# Control.net
KiCad netlist of a schematic drawn in Altium Designer
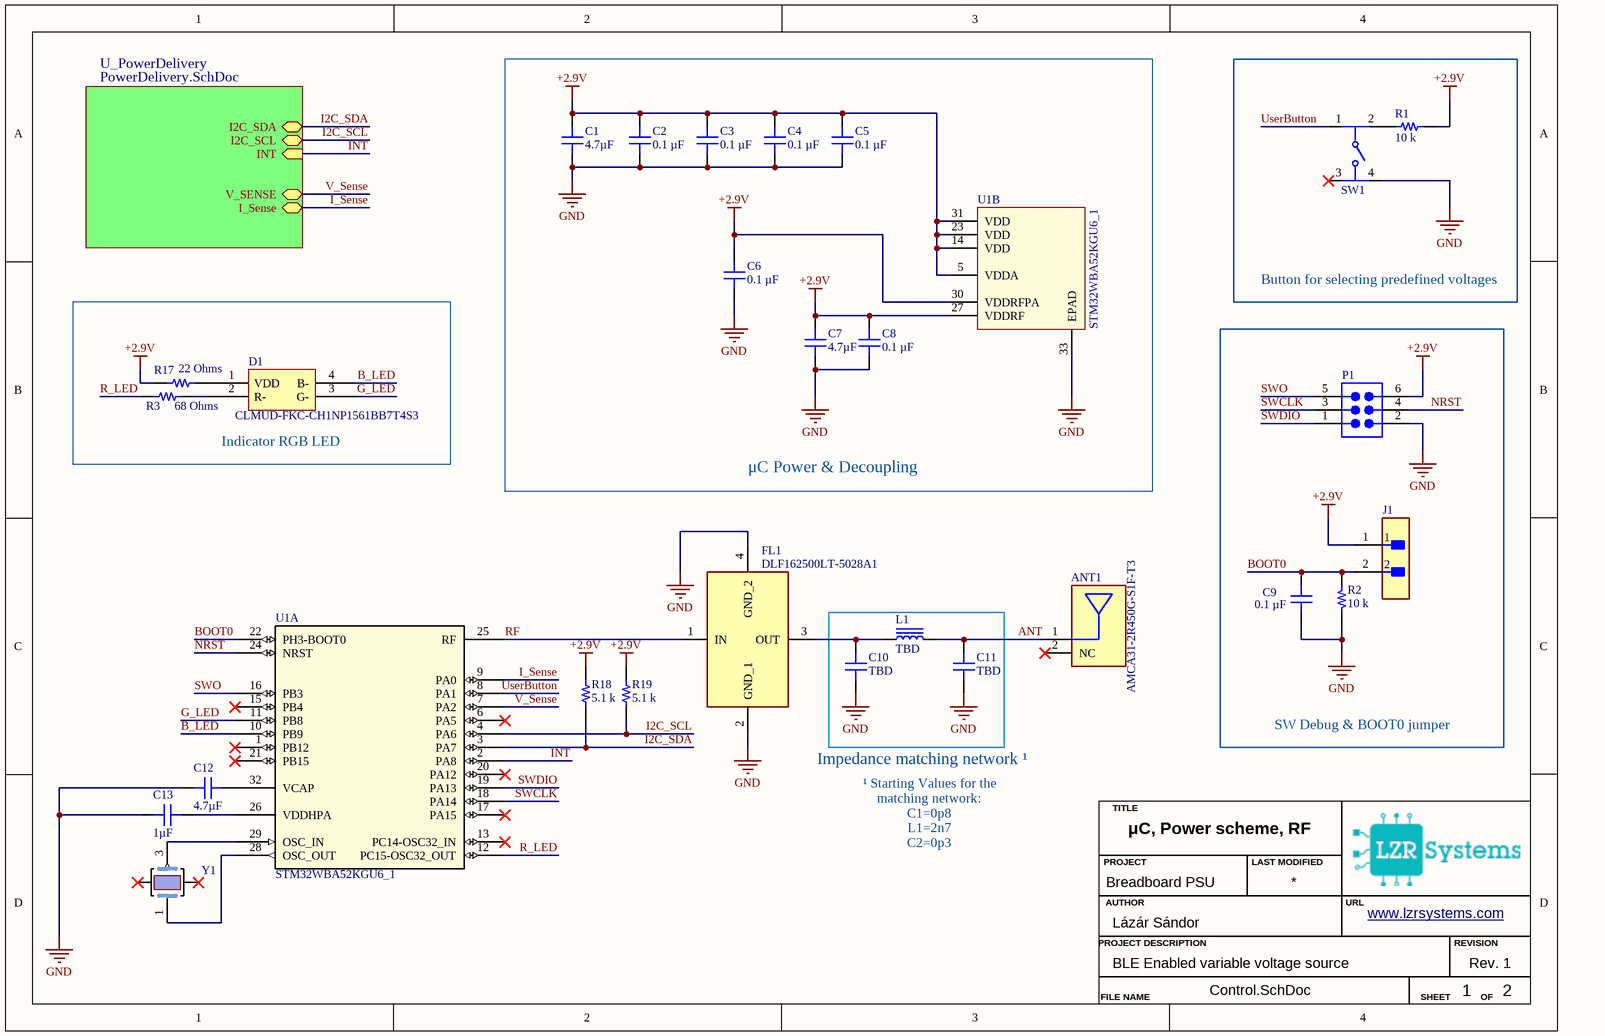
[diagram p0: Control.SchDoc]

(export (version "E")
  (design (tool "Eeschema 10.0.6"))
  (components
    (comp (ref "ANT1")
      (value "AMCA31-2R450G-S1F-T3")
      (footprint "FP-AMCA31-MFG")
      (description "Chip Dielectric Antenna; 1dBi; 2450MHz; T/R")
      (libsource (lib "Sandor Lazar") (part "feefd54aed95757a858c12fc87bd8d5"))
    )
    (comp (ref "C1")
      (value "4.7µF")
      (footprint "CAP 0805_2012")
      (description "CAP CER 4.7UF 10V X5R 0805")
      (fields
        (field (name "PART NUMBER") "0805ZD475KAT2A")
        (field (name "CAPACITANCE") "4.7µF")
        (field (name "MANUFACTURER") "AVX Corporation")
      )
      (libsource (lib "Celestial Altium Library - altium_library") (part "Capacitor"))
    )
    (comp (ref "C2")
      (value "0.1 µF")
      (footprint "CAP 0805_2012")
      (description "CAP CER 0.1UF 50V X7R 0805")
      (fields
        (field (name "PART NUMBER") "KGM21NR71H104MT")
        (field (name "CAPACITANCE") "0.1 µF")
        (field (name "MANUFACTURER") "KYOCERA AVX")
      )
      (libsource (lib "Celestial Altium Library - altium_library") (part "Capacitor"))
    )
    (comp (ref "C3")
      (value "0.1 µF")
      (footprint "CAP 0805_2012")
      (description "CAP CER 0.1UF 50V X7R 0805")
      (fields
        (field (name "PART NUMBER") "KGM21NR71H104MT")
        (field (name "CAPACITANCE") "0.1 µF")
        (field (name "MANUFACTURER") "KYOCERA AVX")
      )
      (libsource (lib "Celestial Altium Library - altium_library") (part "Capacitor"))
    )
    (comp (ref "C4")
      (value "0.1 µF")
      (footprint "CAP 0805_2012")
      (description "CAP CER 0.1UF 50V X7R 0805")
      (fields
        (field (name "PART NUMBER") "KGM21NR71H104MT")
        (field (name "CAPACITANCE") "0.1 µF")
        (field (name "MANUFACTURER") "KYOCERA AVX")
      )
      (libsource (lib "Celestial Altium Library - altium_library") (part "Capacitor"))
    )
    (comp (ref "C5")
      (value "0.1 µF")
      (footprint "CAP 0805_2012")
      (description "CAP CER 0.1UF 50V X7R 0805")
      (fields
        (field (name "PART NUMBER") "KGM21NR71H104MT")
        (field (name "CAPACITANCE") "0.1 µF")
        (field (name "MANUFACTURER") "KYOCERA AVX")
      )
      (libsource (lib "Celestial Altium Library - altium_library") (part "Capacitor"))
    )
    (comp (ref "C6")
      (value "0.1 µF")
      (footprint "CAP 0805_2012")
      (description "CAP CER 0.1UF 50V X7R 0805")
      (fields
        (field (name "PART NUMBER") "KGM21NR71H104MT")
        (field (name "CAPACITANCE") "0.1 µF")
        (field (name "MANUFACTURER") "KYOCERA AVX")
      )
      (libsource (lib "Celestial Altium Library - altium_library") (part "Capacitor"))
    )
    (comp (ref "C7")
      (value "4.7µF")
      (footprint "CAP 0805_2012")
      (description "CAP CER 4.7UF 10V X5R 0805")
      (fields
        (field (name "PART NUMBER") "0805ZD475KAT2A")
        (field (name "CAPACITANCE") "4.7µF")
        (field (name "MANUFACTURER") "AVX Corporation")
      )
      (libsource (lib "Celestial Altium Library - altium_library") (part "Capacitor"))
    )
    (comp (ref "C8")
      (value "0.1 µF")
      (footprint "CAP 0805_2012")
      (description "CAP CER 0.1UF 50V X7R 0805")
      (fields
        (field (name "PART NUMBER") "KGM21NR71H104MT")
        (field (name "CAPACITANCE") "0.1 µF")
        (field (name "MANUFACTURER") "KYOCERA AVX")
      )
      (libsource (lib "Celestial Altium Library - altium_library") (part "Capacitor"))
    )
    (comp (ref "C9")
      (value "0.1 µF")
      (footprint "CAP 0805_2012")
      (description "CAP CER 0.1UF 50V X7R 0805")
      (fields
        (field (name "PART NUMBER") "KGM21NR71H104MT")
        (field (name "CAPACITANCE") "0.1 µF")
        (field (name "MANUFACTURER") "KYOCERA AVX")
      )
      (libsource (lib "Celestial Altium Library - altium_library") (part "Capacitor"))
    )
    (comp (ref "C10")
      (value "3.6 pF")
      (footprint "CAP 0402_1005")
      (description "CAP CER 3.6PF 200V C0G/NP0 0402")
      (fields
        (field (name "PART NUMBER") "600L3R6AT200T")
        (field (name "CAPACITANCE") "TBD")
        (field (name "MANUFACTURER") "American Technical Ceramics")
      )
      (libsource (lib "Celestial Altium Library - altium_library") (part "Capacitor"))
    )
    (comp (ref "C11")
      (value "3.6 pF")
      (footprint "CAP 0402_1005")
      (description "CAP CER 3.6PF 200V C0G/NP0 0402")
      (fields
        (field (name "PART NUMBER") "600L3R6AT200T")
        (field (name "CAPACITANCE") "TBD")
        (field (name "MANUFACTURER") "American Technical Ceramics")
      )
      (libsource (lib "Celestial Altium Library - altium_library") (part "Capacitor"))
    )
    (comp (ref "C12")
      (value "4.7µF")
      (footprint "CAP 0805_2012")
      (description "CAP CER 4.7UF 10V X5R 0805")
      (fields
        (field (name "PART NUMBER") "0805ZD475KAT2A")
        (field (name "CAPACITANCE") "4.7µF")
        (field (name "MANUFACTURER") "AVX Corporation")
      )
      (libsource (lib "Celestial Altium Library - altium_library") (part "Capacitor"))
    )
    (comp (ref "C13")
      (value "1µF")
      (footprint "CAP 0805_2012")
      (description "CAP CER 1UF 25V X7R 0805")
      (fields
        (field (name "PART NUMBER") "08053C105KAT2A")
        (field (name "CAPACITANCE") "1µF")
        (field (name "MANUFACTURER") "AVX Corporation")
      )
      (libsource (lib "Celestial Altium Library - altium_library") (part "Capacitor"))
    )
    (comp (ref "D1")
      (value "CLMUD-FKC-CH1NP1561BB7T4S3")
      (footprint "SON70P150X100-4N")
      (description "Cree LED RGB LED Common Annode If=10mA Vf = 1.9/2.6/2.7")
      (libsource (lib "Sandor Lazar") (part "CLMUD-FKC-CH1NP1561BB7T4S3-Symbol-1"))
    )
    (comp (ref "FL1")
      (value "DLF162500LT-5028A1")
      (footprint "SamacSys:DLF162500LT5028A1")
      (description "Filter")
      (fields (field (name "MOUSER PART NUMBER") "810-DLF16250LT5028A1"))
      (libsource (lib "*") (part "DLF162500LT-5028A1"))
    )
    (comp (ref "J1")
      (value "TSW-102-12-T-S")
      (footprint "FP-TSW-102-12-T-S-MFG")
      (description "Pin Header, Board-to-Board, 2.54 mm, 1 Rows, 2 Contacts, Through Hole, TSW Series")
      (libsource (lib "Sandor Lazar") (part "3bc925449376181038e59eaffc5286c"))
    )
    (comp (ref "L1")
      (value "TBD")
      (footprint "IND 0402_1005")
      (description "FIXED IND 3.9NH 750MA 140MOHM SM")
      (fields
        (field (name "PART NUMBER") "LQG15HS3N9C02D")
        (field (name "MANUFACTURER") "Murata Electronics")
      )
      (libsource (lib "Celestial Altium Library - altium_library") (part "Inductor"))
    )
    (comp (ref "P1")
      (value "MTLW-103-06-G-D-180")
      (footprint "SMTC-MTLW-103-06-X-D-180")
      (description "Pin Header, Board-to-Board, 2.54 mm, 2 Rows, 6 Contacts, Through Hole, MTLW Series")
      (libsource (lib "Sandor Lazar") (part "SMTC-MTLW-103-06-X-D-180"))
    )
    (comp (ref "R1")
      (value "10 k")
      (footprint "RES 0805_2012")
      (description "RES 10K OHM 0.1% 1/10W 0805")
      (fields
        (field (name "PART NUMBER") "RNCS0805BKE10K0")
        (field (name "MANUFACTURER") "Stackpole Electronics Inc")
      )
      (libsource (lib "Celestial Altium Library - altium_library") (part "Resistor"))
    )
    (comp (ref "R2")
      (value "10 k")
      (footprint "RES 0805_2012")
      (description "RES 10K OHM 0.1% 1/10W 0805")
      (fields
        (field (name "PART NUMBER") "RNCS0805BKE10K0")
        (field (name "MANUFACTURER") "Stackpole Electronics Inc")
      )
      (libsource (lib "Celestial Altium Library - altium_library") (part "Resistor"))
    )
    (comp (ref "R3")
      (value "68 Ohms")
      (footprint "YAGEO RES 0805_2012")
      (description "RES 68.1 OHM 1% 1/8W 0805")
      (fields (field (name "PART NUMBER") "RC0805FR-0768R1L") (field (name "MANUFACTURER") "Yageo"))
      (libsource (lib "Celestial Altium Library - altium_library") (part "Resistor"))
    )
    (comp (ref "R17")
      (value "22 Ohms")
      (footprint "RES 0805_2012")
      (description "RES 22 OHM 5% 1/8W 0805")
      (fields (field (name "PART NUMBER") "SFR10EZPJ220") (field (name "MANUFACTURER") "Rohm Semiconductor"))
      (libsource (lib "Celestial Altium Library - altium_library") (part "Resistor"))
    )
    (comp (ref "R18")
      (value "5.1 k")
      (footprint "YAGEO RES 0805_2012")
      (description "RES SMD 5.1K OHM 0.1% 1/8W 0805")
      (fields (field (name "PART NUMBER") "RT0805BRD075K1L") (field (name "MANUFACTURER") "Yageo"))
      (libsource (lib "Celestial Altium Library - altium_library") (part "Resistor"))
    )
    (comp (ref "R19")
      (value "5.1 k")
      (footprint "YAGEO RES 0805_2012")
      (description "RES SMD 5.1K OHM 0.1% 1/8W 0805")
      (fields (field (name "PART NUMBER") "RT0805BRD075K1L") (field (name "MANUFACTURER") "Yageo"))
      (libsource (lib "Celestial Altium Library - altium_library") (part "Resistor"))
    )
    (comp (ref "SW1")
      (value "TL1105AF160Q")
      (footprint "FP-TL1105AF160Q-MFG")
      (description "Switch Tactile N.O. SPST Round Button PC Pins 0.05A 50VDC 1.57N Thru-Hole")
      (libsource (lib "Sandor Lazar") (part "82b636f13fd696edb7519609c0a8a76"))
    )
    (comp (ref "U1")
      (value "STM32WBA52KGU6_1")
      (footprint "UFQFPN-32_STM")
      (fields
        (field (name "MANUFACTURER_PART_NUMBER") "STM32WBA52KGU6")
        (field (name "COPYRIGHT") "Copyright (C) 2025 Ultra Librarian. All rights reserved.")
      )
      (libsource (lib "Sandor Lazar") (part "STM32WBA52KGU6_1"))
    )
    (comp (ref "Y1")
      (value "XRCGB32M000F2P01R0")
      (footprint "SamacSys:XRCGB")
      (description "Crystal or Oscillator")
      (fields (field (name "MOUSER PART NUMBER") "81-XRCGB32M000F2P01R"))
      (libsource (lib "SamacSys") (part "XRCGB32M000F2P01R0"))
    )
  )
  (nets
    (net (code "1") (name "+2.9V") (class "Default")
      (node (ref "C1") (pin "2") (pinfunction "2_2") (pintype "passive"))
      (node (ref "C2") (pin "2") (pinfunction "2_2") (pintype "passive"))
      (node (ref "C3") (pin "2") (pinfunction "2_2") (pintype "passive"))
      (node (ref "C4") (pin "2") (pinfunction "2_2") (pintype "passive"))
      (node (ref "C5") (pin "2") (pinfunction "2_2") (pintype "passive"))
      (node (ref "C6") (pin "2") (pinfunction "2_2") (pintype "passive"))
      (node (ref "C7") (pin "2") (pinfunction "2_2") (pintype "passive"))
      (node (ref "C8") (pin "2") (pinfunction "2_2") (pintype "passive"))
      (node (ref "J1") (pin "1") (pinfunction "1_1") (pintype "passive"))
      (node (ref "P1") (pin "6") (pinfunction "6_6") (pintype "passive"))
      (node (ref "R1") (pin "2") (pinfunction "2_2") (pintype "passive"))
      (node (ref "R17") (pin "2") (pinfunction "2_2") (pintype "passive"))
      (node (ref "R18") (pin "2") (pinfunction "2_2") (pintype "passive"))
      (node (ref "R19") (pin "2") (pinfunction "2_2") (pintype "passive"))
      (node (ref "U1") (pin "14") (pinfunction "VDD_14") (pintype "power_in"))
      (node (ref "U1") (pin "23") (pinfunction "VDD_23") (pintype "power_in"))
      (node (ref "U1") (pin "27") (pinfunction "VDDRF_27") (pintype "power_in"))
      (node (ref "U1") (pin "30") (pinfunction "VDDRFPA_30") (pintype "power_in"))
      (node (ref "U1") (pin "31") (pinfunction "VDD_31") (pintype "power_in"))
      (node (ref "U1") (pin "5") (pinfunction "VDDA_5") (pintype "power_in"))
    )
    (net (code "2") (name "/ANT") (class "Default")
      (node (ref "ANT1") (pin "1") (pinfunction "Feed_Point_1") (pintype "passive"))
      (node (ref "C11") (pin "2") (pinfunction "2_2") (pintype "passive"))
      (node (ref "L1") (pin "2") (pinfunction "2_2") (pintype "passive"))
    )
    (net (code "3") (name "/BOOT0") (class "Default")
      (node (ref "C9") (pin "2") (pinfunction "2_2") (pintype "passive"))
      (node (ref "J1") (pin "2") (pinfunction "2_2") (pintype "passive"))
      (node (ref "R2") (pin "2") (pinfunction "2_2") (pintype "passive"))
      (node (ref "U1") (pin "22") (pinfunction "PH3-BOOT0_22") (pintype "bidirectional"))
    )
    (net (code "4") (name "/B_LED") (class "Default")
      (node (ref "D1") (pin "4") (pinfunction "B-_4") (pintype "passive"))
      (node (ref "U1") (pin "10") (pinfunction "PB9_10") (pintype "bidirectional"))
    )
    (net (code "5") (name "/G_LED") (class "Default")
      (node (ref "D1") (pin "3") (pinfunction "G-_3") (pintype "passive"))
      (node (ref "U1") (pin "11") (pinfunction "PB8_11") (pintype "bidirectional"))
    )
    (net (code "6") (name "/I2C_SCL") (class "Default")
      (node (ref "R19") (pin "1") (pinfunction "1_1") (pintype "passive"))
      (node (ref "U1") (pin "4") (pinfunction "PA6_4") (pintype "bidirectional"))
    )
    (net (code "7") (name "/I2C_SDA") (class "Default")
      (node (ref "R18") (pin "1") (pinfunction "1_1") (pintype "passive"))
      (node (ref "U1") (pin "3") (pinfunction "PA7_3") (pintype "bidirectional"))
    )
    (net (code "8") (name "/INT") (class "Default")
      (node (ref "U1") (pin "2") (pinfunction "PA8_2") (pintype "bidirectional"))
    )
    (net (code "9") (name "/I_Sense") (class "Default")
      (node (ref "U1") (pin "9") (pinfunction "PA0_9") (pintype "bidirectional"))
    )
    (net (code "10") (name "/NRST") (class "Default")
      (node (ref "P1") (pin "4") (pinfunction "4_4") (pintype "passive"))
      (node (ref "U1") (pin "24") (pinfunction "NRST_24") (pintype "bidirectional"))
    )
    (net (code "11") (name "/RF") (class "Default")
      (node (ref "FL1") (pin "1") (pinfunction "IN_1") (pintype "passive"))
      (node (ref "U1") (pin "25") (pinfunction "RF_25") (pintype "passive"))
    )
    (net (code "12") (name "/R_LED") (class "Default")
      (node (ref "R3") (pin "1") (pinfunction "1_1") (pintype "passive"))
      (node (ref "U1") (pin "12") (pinfunction "PC15-OSC32_OUT_12") (pintype "bidirectional"))
    )
    (net (code "13") (name "/SWCLK") (class "Default")
      (node (ref "P1") (pin "3") (pinfunction "3_3") (pintype "passive"))
      (node (ref "U1") (pin "18") (pinfunction "PA14_18") (pintype "bidirectional"))
    )
    (net (code "14") (name "/SWDIO") (class "Default")
      (node (ref "P1") (pin "1") (pinfunction "1_1") (pintype "passive"))
      (node (ref "U1") (pin "19") (pinfunction "PA13_19") (pintype "bidirectional"))
    )
    (net (code "15") (name "/SWO") (class "Default")
      (node (ref "P1") (pin "5") (pinfunction "5_5") (pintype "passive"))
      (node (ref "U1") (pin "16") (pinfunction "PB3_16") (pintype "bidirectional"))
    )
    (net (code "16") (name "/UserButton") (class "Default")
      (node (ref "SW1") (pin "1") (pinfunction "1_1") (pintype "passive"))
      (node (ref "U1") (pin "8") (pinfunction "PA1_8") (pintype "bidirectional"))
    )
    (net (code "17") (name "/V_Sense") (class "Default")
      (node (ref "U1") (pin "7") (pinfunction "PA2_7") (pintype "bidirectional"))
    )
    (net (code "18") (name "GND") (class "Default")
      (node (ref "C1") (pin "1") (pinfunction "1_1") (pintype "passive"))
      (node (ref "C10") (pin "1") (pinfunction "1_1") (pintype "passive"))
      (node (ref "C11") (pin "1") (pinfunction "1_1") (pintype "passive"))
      (node (ref "C12") (pin "1") (pinfunction "1_1") (pintype "passive"))
      (node (ref "C13") (pin "2") (pinfunction "2_2") (pintype "passive"))
      (node (ref "C2") (pin "1") (pinfunction "1_1") (pintype "passive"))
      (node (ref "C3") (pin "1") (pinfunction "1_1") (pintype "passive"))
      (node (ref "C4") (pin "1") (pinfunction "1_1") (pintype "passive"))
      (node (ref "C5") (pin "1") (pinfunction "1_1") (pintype "passive"))
      (node (ref "C6") (pin "1") (pinfunction "1_1") (pintype "passive"))
      (node (ref "C7") (pin "1") (pinfunction "1_1") (pintype "passive"))
      (node (ref "C8") (pin "1") (pinfunction "1_1") (pintype "passive"))
      (node (ref "C9") (pin "1") (pinfunction "1_1") (pintype "passive"))
      (node (ref "FL1") (pin "2") (pinfunction "GND_1_2") (pintype "passive"))
      (node (ref "FL1") (pin "4") (pinfunction "GND_2_4") (pintype "passive"))
      (node (ref "P1") (pin "2") (pinfunction "2_2") (pintype "passive"))
      (node (ref "R2") (pin "1") (pinfunction "1_1") (pintype "passive"))
      (node (ref "SW1") (pin "4") (pinfunction "4_4") (pintype "passive"))
      (node (ref "U1") (pin "33") (pinfunction "EPAD_33") (pintype "passive"))
    )
    (net (code "19") (name "Net-(D1-R-)") (class "Default")
      (node (ref "D1") (pin "2") (pinfunction "R-_2") (pintype "passive"))
      (node (ref "R3") (pin "2") (pinfunction "2_2") (pintype "passive"))
    )
    (net (code "20") (name "Net-(D1-VDD)") (class "Default")
      (node (ref "D1") (pin "1") (pinfunction "VDD_1") (pintype "passive"))
      (node (ref "R17") (pin "1") (pinfunction "1_1") (pintype "passive"))
    )
    (net (code "21") (name "Net-(FL1-OUT)") (class "Default")
      (node (ref "C10") (pin "2") (pinfunction "2_2") (pintype "passive"))
      (node (ref "FL1") (pin "3") (pinfunction "OUT_3") (pintype "passive"))
      (node (ref "L1") (pin "1") (pinfunction "1_1") (pintype "passive"))
    )
    (net (code "22") (name "Net-(R1-Pad1)") (class "Default")
      (node (ref "R1") (pin "1") (pinfunction "1_1") (pintype "passive"))
      (node (ref "SW1") (pin "2") (pinfunction "2_2") (pintype "passive"))
    )
    (net (code "23") (name "Net-(U1A-OSC_IN)") (class "Default")
      (node (ref "U1") (pin "29") (pinfunction "OSC_IN_29") (pintype "input"))
      (node (ref "Y1") (pin "3") (pinfunction "XTAL_2_3") (pintype "output"))
    )
    (net (code "24") (name "Net-(U1A-OSC_OUT)") (class "Default")
      (node (ref "U1") (pin "28") (pinfunction "OSC_OUT_28") (pintype "output"))
      (node (ref "Y1") (pin "1") (pinfunction "XTAL_1_1") (pintype "passive"))
    )
    (net (code "25") (name "Net-(U1A-VCAP)") (class "Default")
      (node (ref "C12") (pin "2") (pinfunction "2_2") (pintype "passive"))
      (node (ref "U1") (pin "32") (pinfunction "VCAP_32") (pintype "power_in"))
    )
    (net (code "26") (name "Net-(U1A-VDDHPA)") (class "Default")
      (node (ref "C13") (pin "1") (pinfunction "1_1") (pintype "passive"))
      (node (ref "U1") (pin "26") (pinfunction "VDDHPA_26") (pintype "power_in"))
    )
    (net (code "27") (name "unconnected-(ANT1-NC-Pad2)") (class "Default")
      (node (ref "ANT1") (pin "2") (pinfunction "NC_2") (pintype "passive+no_connect"))
    )
    (net (code "28") (name "unconnected-(SW1-Pad3)") (class "Default")
      (node (ref "SW1") (pin "3") (pinfunction "3_3") (pintype "passive+no_connect"))
    )
    (net (code "29") (name "unconnected-(U1A-PA5-Pad6)") (class "Default")
      (node (ref "U1") (pin "6") (pinfunction "PA5_6") (pintype "bidirectional+no_connect"))
    )
    (net (code "30") (name "unconnected-(U1A-PA12-Pad20)") (class "Default")
      (node (ref "U1") (pin "20") (pinfunction "PA12_20") (pintype "bidirectional+no_connect"))
    )
    (net (code "31") (name "unconnected-(U1A-PA15-Pad17)") (class "Default")
      (node (ref "U1") (pin "17") (pinfunction "PA15_17") (pintype "bidirectional+no_connect"))
    )
    (net (code "32") (name "unconnected-(U1A-PB4-Pad15)") (class "Default")
      (node (ref "U1") (pin "15") (pinfunction "PB4_15") (pintype "bidirectional+no_connect"))
    )
    (net (code "33") (name "unconnected-(U1A-PB12-Pad1)") (class "Default")
      (node (ref "U1") (pin "1") (pinfunction "PB12_1") (pintype "bidirectional+no_connect"))
    )
    (net (code "34") (name "unconnected-(U1A-PB15-Pad21)") (class "Default")
      (node (ref "U1") (pin "21") (pinfunction "PB15_21") (pintype "bidirectional+no_connect"))
    )
    (net (code "35") (name "unconnected-(U1A-PC14-OSC32_IN-Pad13)") (class "Default")
      (node (ref "U1") (pin "13") (pinfunction "PC14-OSC32_IN_13") (pintype "bidirectional+no_connect"))
    )
    (net (code "36") (name "unconnected-(Y1-NC_1-Pad2)") (class "Default")
      (node (ref "Y1") (pin "2") (pinfunction "NC_1_2") (pintype "passive+no_connect"))
    )
    (net (code "37") (name "unconnected-(Y1-Pad4)") (class "Default")
      (node (ref "Y1") (pin "4") (pintype "passive+no_connect"))
    )
  )
)
